# smart_prototyping2.net
KiCad netlist of a schematic drawn in EAGLE
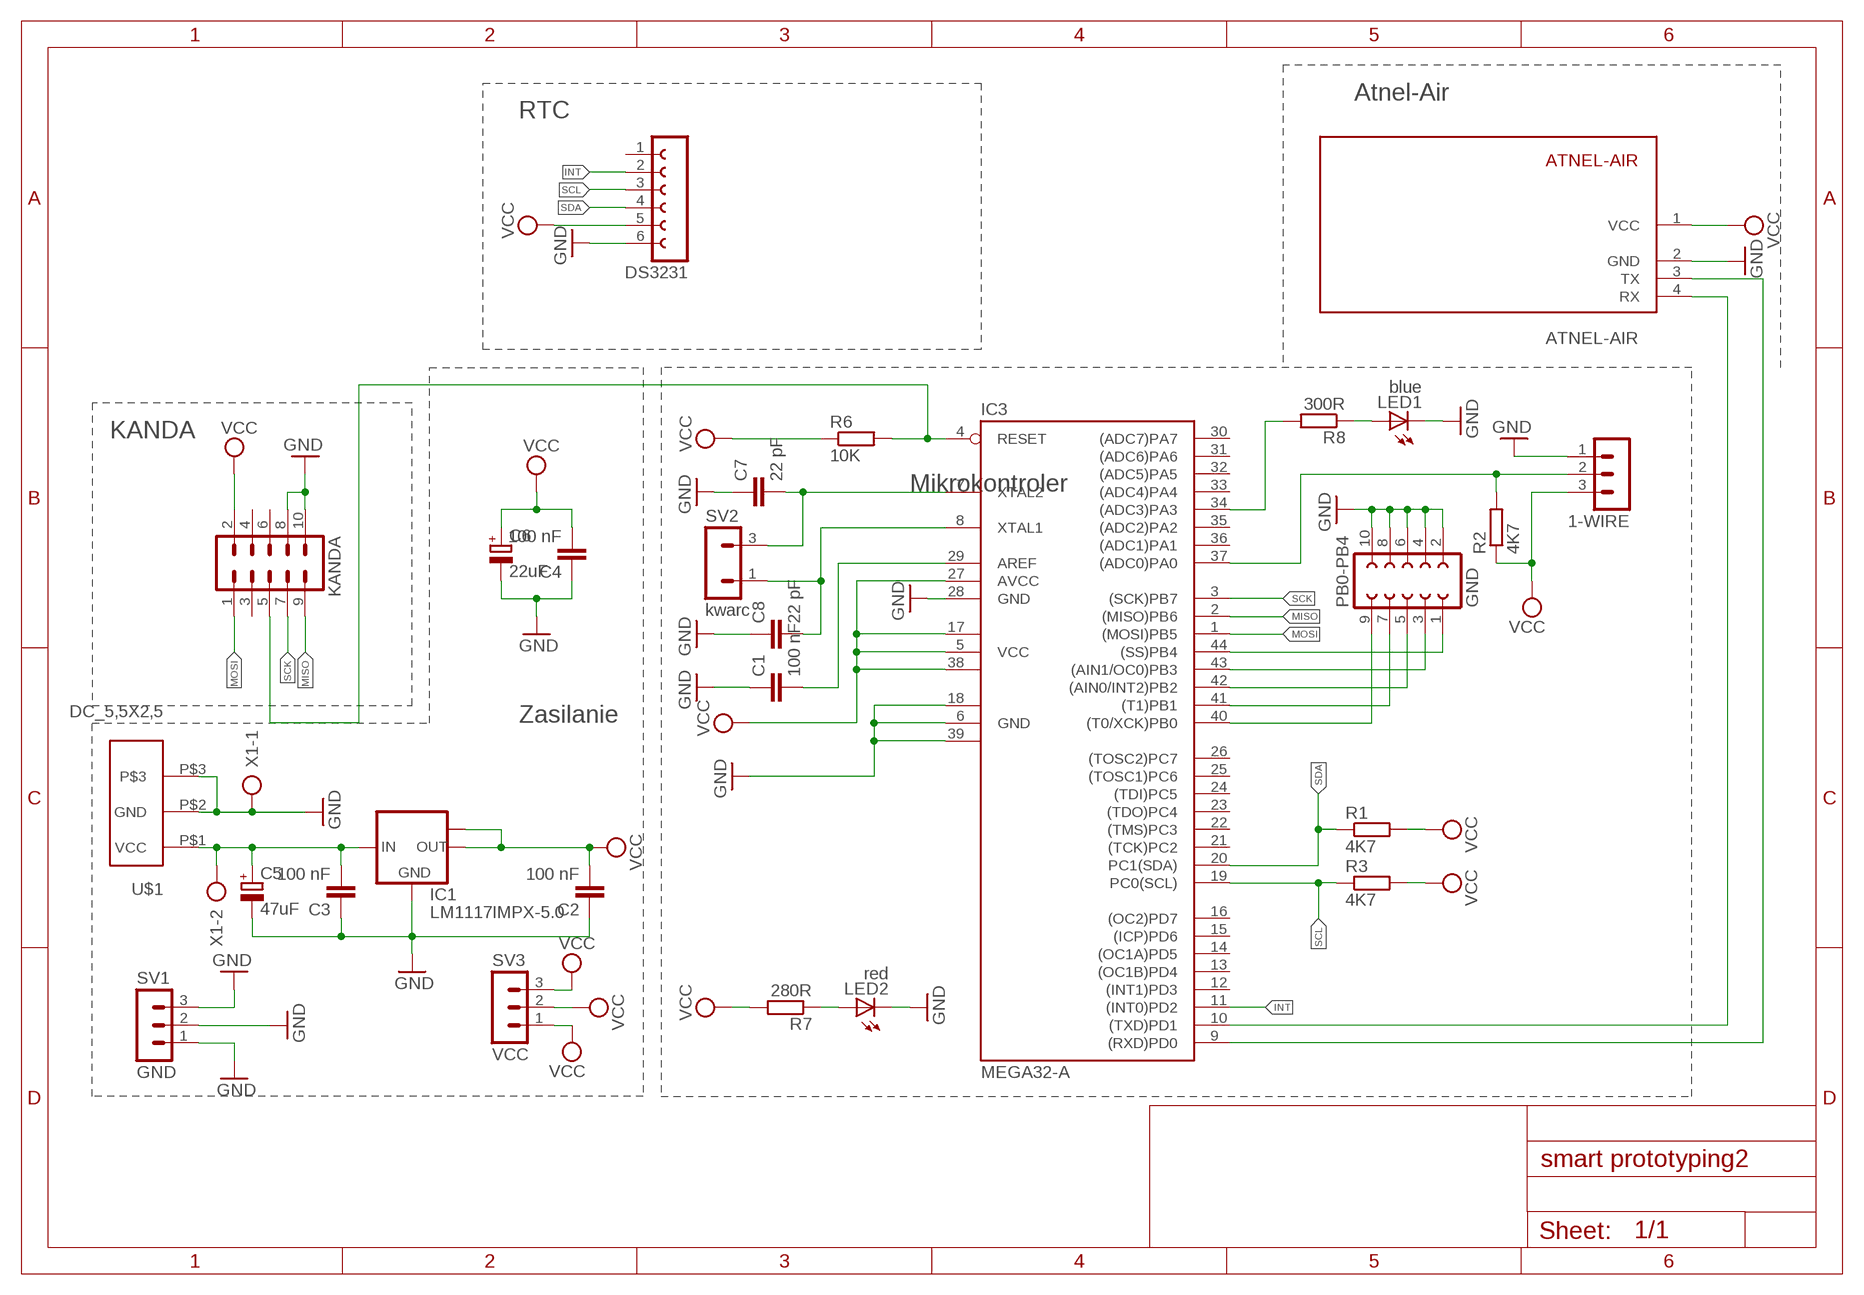
[diagram p0: schematic, sheet 1]

(export (version "E")
  (design (tool "Eeschema 10.0.6"))
  (components
    (comp (ref "1-WIRE")
      (value "MA03-1")
      (footprint "eagle-import:MA03-1")
      (libsource (lib "eagle-import") (part "MA03-1"))
    )
    (comp (ref "ATNEL-AIR")
      (value "ATNEL-AIR")
      (footprint "eagle-import:ATNEL-AIR")
      (libsource (lib "eagle-import") (part "ATNEL-AIR"))
    )
    (comp (ref "C1")
      (value "100 nF")
      (footprint "eagle-import:C0805")
      (libsource (lib "eagle-import") (part "C-EUC0805"))
    )
    (comp (ref "C2")
      (value "100 nF")
      (footprint "eagle-import:C0805")
      (libsource (lib "eagle-import") (part "C-EUC0805"))
    )
    (comp (ref "C3")
      (value "100 nF")
      (footprint "eagle-import:C0805")
      (libsource (lib "eagle-import") (part "C-EUC0805"))
    )
    (comp (ref "C4")
      (value "100 nF")
      (footprint "eagle-import:C0805")
      (libsource (lib "eagle-import") (part "C-EUC0805"))
    )
    (comp (ref "C5")
      (value "47uF")
      (footprint "eagle-import:B45181A")
      (libsource (lib "eagle-import") (part "CPOL-EUB45181A"))
    )
    (comp (ref "C6")
      (value "22uF")
      (footprint "eagle-import:B45181A")
      (libsource (lib "eagle-import") (part "CPOL-EUB45181A"))
    )
    (comp (ref "C7")
      (value "22 pF")
      (footprint "eagle-import:C0805")
      (libsource (lib "eagle-import") (part "C-EUC0805"))
    )
    (comp (ref "C8")
      (value "22 pF")
      (footprint "eagle-import:C0805")
      (libsource (lib "eagle-import") (part "C-EUC0805"))
    )
    (comp (ref "DS3231")
      (value "FE06-1")
      (footprint "eagle-import:FE06")
      (libsource (lib "eagle-import") (part "FE06-1"))
    )
    (comp (ref "IC1")
      (value "LM1117IMPX-5.0")
      (footprint "eagle-import:SOT223")
      (libsource (lib "eagle-import") (part "LM1117IMPX-5.0"))
    )
    (comp (ref "IC3")
      (value "MEGA32-A")
      (footprint "eagle-import:TQFP44")
      (fields (field (name "MPN") "ATMEGA32-16AU"))
      (libsource (lib "eagle-import") (part "MEGA32-A"))
    )
    (comp (ref "KANDA")
      (value "ML10")
      (footprint "eagle-import:ML10")
      (libsource (lib "eagle-import") (part "ML10"))
    )
    (comp (ref "LED1")
      (value "blue")
      (footprint "eagle-import:CHIPLED_1206")
      (libsource (lib "eagle-import") (part "LEDCHIPLED_1206"))
    )
    (comp (ref "LED2")
      (value "red")
      (footprint "eagle-import:CHIPLED_1206")
      (libsource (lib "eagle-import") (part "LEDCHIPLED_1206"))
    )
    (comp (ref "PB0-PB4")
      (value "GND")
      (footprint "eagle-import:FE05-2")
      (libsource (lib "eagle-import") (part "FE05-2"))
    )
    (comp (ref "R1")
      (value "4K7")
      (footprint "eagle-import:R1206W")
      (libsource (lib "eagle-import") (part "R-EU_R1206W"))
    )
    (comp (ref "R2")
      (value "4K7")
      (footprint "eagle-import:R1206W")
      (libsource (lib "eagle-import") (part "R-EU_R1206W"))
    )
    (comp (ref "R3")
      (value "4K7")
      (footprint "eagle-import:R1206W")
      (libsource (lib "eagle-import") (part "R-EU_R1206W"))
    )
    (comp (ref "R6")
      (value "10K")
      (footprint "eagle-import:R1206W")
      (libsource (lib "eagle-import") (part "R-EU_R1206W"))
    )
    (comp (ref "R7")
      (value "280R")
      (footprint "eagle-import:R1206W")
      (libsource (lib "eagle-import") (part "R-EU_R1206W"))
    )
    (comp (ref "R8")
      (value "300R")
      (footprint "eagle-import:R1206W")
      (libsource (lib "eagle-import") (part "R-EU_R1206W"))
    )
    (comp (ref "SV1")
      (value "GND")
      (footprint "eagle-import:MA03-1")
      (libsource (lib "eagle-import") (part "MA03-1"))
    )
    (comp (ref "SV2")
      (value "kwarc")
      (footprint "eagle-import:MA03-1")
      (libsource (lib "eagle-import") (part "con-lstb-wachcio_MA03-1"))
    )
    (comp (ref "SV3")
      (value "VCC")
      (footprint "eagle-import:MA03-1")
      (libsource (lib "eagle-import") (part "MA03-1"))
    )
    (comp (ref "U$1")
      (value "DC_5,5X2,5")
      (footprint "eagle-import:DC_5,5X2,5")
      (libsource (lib "eagle-import") (part "DC_5,5X2,5"))
    )
    (comp (ref "X1")
      (value "AK500/2")
      (footprint "eagle-import:AK500_2")
      (libsource (lib "eagle-import") (part "AK500/2"))
    )
  )
  (nets
    (net (code "1") (name "GND") (class "Default")
      (node (ref "1-WIRE") (pin "1") (pinfunction "1_1") (pintype "passive"))
      (node (ref "ATNEL-AIR") (pin "2") (pinfunction "GND_2") (pintype "bidirectional"))
      (node (ref "C1") (pin "1") (pinfunction "1_1") (pintype "passive"))
      (node (ref "C2") (pin "1") (pinfunction "1_1") (pintype "passive"))
      (node (ref "C3") (pin "1") (pinfunction "1_1") (pintype "passive"))
      (node (ref "C4") (pin "1") (pinfunction "1_1") (pintype "passive"))
      (node (ref "C5") (pin "-") (pinfunction "-_-") (pintype "passive"))
      (node (ref "C6") (pin "-") (pinfunction "-_-") (pintype "passive"))
      (node (ref "C7") (pin "1") (pinfunction "1_1") (pintype "passive"))
      (node (ref "C8") (pin "1") (pinfunction "1_1") (pintype "passive"))
      (node (ref "DS3231") (pin "6") (pinfunction "6_6") (pintype "passive"))
      (node (ref "IC1") (pin "1") (pinfunction "GND_1") (pintype "input"))
      (node (ref "IC3") (pin "18") (pinfunction "GND1_18") (pintype "power_in"))
      (node (ref "IC3") (pin "28") (pinfunction "GND_28") (pintype "power_in"))
      (node (ref "IC3") (pin "39") (pinfunction "GND2_39") (pintype "power_in"))
      (node (ref "IC3") (pin "6") (pinfunction "GND_6") (pintype "power_in"))
      (node (ref "KANDA") (pin "10") (pinfunction "10_10") (pintype "passive"))
      (node (ref "KANDA") (pin "8") (pinfunction "8_8") (pintype "passive"))
      (node (ref "LED1") (pin "C") (pinfunction "C_C") (pintype "passive"))
      (node (ref "LED2") (pin "C") (pinfunction "C_C") (pintype "passive"))
      (node (ref "PB0-PB4") (pin "10") (pinfunction "10_10") (pintype "passive"))
      (node (ref "PB0-PB4") (pin "2") (pinfunction "2_2") (pintype "passive"))
      (node (ref "PB0-PB4") (pin "4") (pinfunction "4_4") (pintype "passive"))
      (node (ref "PB0-PB4") (pin "6") (pinfunction "6_6") (pintype "passive"))
      (node (ref "PB0-PB4") (pin "8") (pinfunction "8_8") (pintype "passive"))
      (node (ref "SV1") (pin "1") (pinfunction "1_1") (pintype "passive"))
      (node (ref "SV1") (pin "2") (pinfunction "2_2") (pintype "passive"))
      (node (ref "SV1") (pin "3") (pinfunction "3_3") (pintype "passive"))
      (node (ref "U$1") (pin "P$2") (pinfunction "GND_P$2") (pintype "bidirectional"))
      (node (ref "U$1") (pin "P$3") (pinfunction "P$3_P$3") (pintype "bidirectional"))
      (node (ref "X1") (pin "1") (pinfunction "KL_1") (pintype "passive"))
    )
    (net (code "2") (name "INT") (class "Default")
      (node (ref "DS3231") (pin "2") (pinfunction "2_2") (pintype "passive"))
      (node (ref "IC3") (pin "11") (pinfunction "(INT0)PD2_11") (pintype "bidirectional"))
    )
    (net (code "3") (name "MISO") (class "Default")
      (node (ref "IC3") (pin "2") (pinfunction "(MISO)PB6_2") (pintype "bidirectional"))
      (node (ref "KANDA") (pin "9") (pinfunction "9_9") (pintype "passive"))
    )
    (net (code "4") (name "MOSI") (class "Default")
      (node (ref "IC3") (pin "1") (pinfunction "(MOSI)PB5_1") (pintype "bidirectional"))
      (node (ref "KANDA") (pin "1") (pinfunction "1_1") (pintype "passive"))
    )
    (net (code "5") (name "Net-(ATNEL-AIR-RX)") (class "Default")
      (node (ref "ATNEL-AIR") (pin "4") (pinfunction "RX_4") (pintype "output"))
      (node (ref "IC3") (pin "10") (pinfunction "(TXD)PD1_10") (pintype "bidirectional"))
    )
    (net (code "6") (name "Net-(ATNEL-AIR-TX)") (class "Default")
      (node (ref "ATNEL-AIR") (pin "3") (pinfunction "TX_3") (pintype "input"))
      (node (ref "IC3") (pin "9") (pinfunction "(RXD)PD0_9") (pintype "bidirectional"))
    )
    (net (code "7") (name "Net-(IC1-IN)") (class "Default")
      (node (ref "C3") (pin "2") (pinfunction "2_2") (pintype "passive"))
      (node (ref "C5") (pin "+") (pinfunction "+_+") (pintype "passive"))
      (node (ref "IC1") (pin "3") (pinfunction "IN_3") (pintype "input"))
      (node (ref "U$1") (pin "P$1") (pinfunction "VCC_P$1") (pintype "bidirectional"))
      (node (ref "X1") (pin "2") (pinfunction "KL_2") (pintype "passive"))
    )
    (net (code "8") (name "Net-(IC3-(ADC0)PA0)") (class "Default")
      (node (ref "1-WIRE") (pin "2") (pinfunction "2_2") (pintype "passive"))
      (node (ref "IC3") (pin "37") (pinfunction "(ADC0)PA0_37") (pintype "bidirectional"))
      (node (ref "R2") (pin "2") (pinfunction "2_2") (pintype "passive"))
    )
    (net (code "9") (name "Net-(IC3-(ADC3)PA3)") (class "Default")
      (node (ref "IC3") (pin "34") (pinfunction "(ADC3)PA3_34") (pintype "bidirectional"))
      (node (ref "R8") (pin "2") (pinfunction "2_2") (pintype "passive"))
    )
    (net (code "10") (name "Net-(IC3-(AIN0{slash}INT2)PB2)") (class "Default")
      (node (ref "IC3") (pin "42") (pinfunction "(AIN0/INT2)PB2_42") (pintype "bidirectional"))
      (node (ref "PB0-PB4") (pin "5") (pinfunction "5_5") (pintype "passive"))
    )
    (net (code "11") (name "Net-(IC3-(AIN1{slash}OC0)PB3)") (class "Default")
      (node (ref "IC3") (pin "43") (pinfunction "(AIN1/OC0)PB3_43") (pintype "bidirectional"))
      (node (ref "PB0-PB4") (pin "3") (pinfunction "3_3") (pintype "passive"))
    )
    (net (code "12") (name "Net-(IC3-(SS)PB4)") (class "Default")
      (node (ref "IC3") (pin "44") (pinfunction "(SS)PB4_44") (pintype "bidirectional"))
      (node (ref "PB0-PB4") (pin "1") (pinfunction "1_1") (pintype "passive"))
    )
    (net (code "13") (name "Net-(IC3-(T0{slash}XCK)PB0)") (class "Default")
      (node (ref "IC3") (pin "40") (pinfunction "(T0/XCK)PB0_40") (pintype "bidirectional"))
      (node (ref "PB0-PB4") (pin "9") (pinfunction "9_9") (pintype "passive"))
    )
    (net (code "14") (name "Net-(IC3-(T1)PB1)") (class "Default")
      (node (ref "IC3") (pin "41") (pinfunction "(T1)PB1_41") (pintype "bidirectional"))
      (node (ref "PB0-PB4") (pin "7") (pinfunction "7_7") (pintype "passive"))
    )
    (net (code "15") (name "Net-(IC3-AREF)") (class "Default")
      (node (ref "C1") (pin "2") (pinfunction "2_2") (pintype "passive"))
      (node (ref "IC3") (pin "29") (pinfunction "AREF_29") (pintype "passive"))
    )
    (net (code "16") (name "Net-(IC3-RESET)") (class "Default")
      (node (ref "IC3") (pin "4") (pinfunction "RESET_4") (pintype "input"))
      (node (ref "KANDA") (pin "5") (pinfunction "5_5") (pintype "passive"))
      (node (ref "R6") (pin "2") (pinfunction "2_2") (pintype "passive"))
    )
    (net (code "17") (name "Net-(IC3-XTAL1)") (class "Default")
      (node (ref "C8") (pin "2") (pinfunction "2_2") (pintype "passive"))
      (node (ref "IC3") (pin "8") (pinfunction "XTAL1_8") (pintype "bidirectional"))
      (node (ref "SV2") (pin "1") (pinfunction "1_1") (pintype "passive"))
    )
    (net (code "18") (name "Net-(IC3-XTAL2)") (class "Default")
      (node (ref "C7") (pin "2") (pinfunction "2_2") (pintype "passive"))
      (node (ref "IC3") (pin "7") (pinfunction "XTAL2_7") (pintype "bidirectional"))
      (node (ref "SV2") (pin "3") (pinfunction "3_3") (pintype "passive"))
    )
    (net (code "19") (name "Net-(LED1-PadA)") (class "Default")
      (node (ref "LED1") (pin "A") (pinfunction "A_A") (pintype "passive"))
      (node (ref "R8") (pin "1") (pinfunction "1_1") (pintype "passive"))
    )
    (net (code "20") (name "Net-(LED2-PadA)") (class "Default")
      (node (ref "LED2") (pin "A") (pinfunction "A_A") (pintype "passive"))
      (node (ref "R7") (pin "1") (pinfunction "1_1") (pintype "passive"))
    )
    (net (code "21") (name "SCK") (class "Default")
      (node (ref "IC3") (pin "3") (pinfunction "(SCK)PB7_3") (pintype "bidirectional"))
      (node (ref "KANDA") (pin "7") (pinfunction "7_7") (pintype "passive"))
    )
    (net (code "22") (name "SCL") (class "Default")
      (node (ref "DS3231") (pin "3") (pinfunction "3_3") (pintype "passive"))
      (node (ref "IC3") (pin "19") (pinfunction "PC0(SCL)_19") (pintype "bidirectional"))
      (node (ref "R3") (pin "1") (pinfunction "1_1") (pintype "passive"))
    )
    (net (code "23") (name "SDA") (class "Default")
      (node (ref "DS3231") (pin "4") (pinfunction "4_4") (pintype "passive"))
      (node (ref "IC3") (pin "20") (pinfunction "PC1(SDA)_20") (pintype "bidirectional"))
      (node (ref "R1") (pin "1") (pinfunction "1_1") (pintype "passive"))
    )
    (net (code "24") (name "VCC") (class "Default")
      (node (ref "1-WIRE") (pin "3") (pinfunction "3_3") (pintype "passive"))
      (node (ref "ATNEL-AIR") (pin "1") (pinfunction "VCC_1") (pintype "bidirectional"))
      (node (ref "C2") (pin "2") (pinfunction "2_2") (pintype "passive"))
      (node (ref "C4") (pin "2") (pinfunction "2_2") (pintype "passive"))
      (node (ref "C6") (pin "+") (pinfunction "+_+") (pintype "passive"))
      (node (ref "DS3231") (pin "5") (pinfunction "5_5") (pintype "passive"))
      (node (ref "IC1") (pin "2") (pinfunction "OUT_2") (pintype "passive"))
      (node (ref "IC1") (pin "TAB") (pinfunction "OUT1_TAB") (pintype "passive"))
      (node (ref "IC3") (pin "17") (pinfunction "VCC1_17") (pintype "power_in"))
      (node (ref "IC3") (pin "27") (pinfunction "AVCC_27") (pintype "power_in"))
      (node (ref "IC3") (pin "38") (pinfunction "VCC2_38") (pintype "power_in"))
      (node (ref "IC3") (pin "5") (pinfunction "VCC_5") (pintype "power_in"))
      (node (ref "KANDA") (pin "2") (pinfunction "2_2") (pintype "passive"))
      (node (ref "R1") (pin "2") (pinfunction "2_2") (pintype "passive"))
      (node (ref "R2") (pin "1") (pinfunction "1_1") (pintype "passive"))
      (node (ref "R3") (pin "2") (pinfunction "2_2") (pintype "passive"))
      (node (ref "R6") (pin "1") (pinfunction "1_1") (pintype "passive"))
      (node (ref "R7") (pin "2") (pinfunction "2_2") (pintype "passive"))
      (node (ref "SV3") (pin "1") (pinfunction "1_1") (pintype "passive"))
      (node (ref "SV3") (pin "2") (pinfunction "2_2") (pintype "passive"))
      (node (ref "SV3") (pin "3") (pinfunction "3_3") (pintype "passive"))
    )
    (net (code "25") (name "unconnected-(DS3231-Pad1)") (class "Default")
      (node (ref "DS3231") (pin "1") (pinfunction "1_1") (pintype "passive"))
    )
    (net (code "26") (name "unconnected-(IC3-(ADC1)PA1-Pad36)") (class "Default")
      (node (ref "IC3") (pin "36") (pinfunction "(ADC1)PA1_36") (pintype "bidirectional"))
    )
    (net (code "27") (name "unconnected-(IC3-(ADC2)PA2-Pad35)") (class "Default")
      (node (ref "IC3") (pin "35") (pinfunction "(ADC2)PA2_35") (pintype "bidirectional"))
    )
    (net (code "28") (name "unconnected-(IC3-(ADC4)PA4-Pad33)") (class "Default")
      (node (ref "IC3") (pin "33") (pinfunction "(ADC4)PA4_33") (pintype "bidirectional"))
    )
    (net (code "29") (name "unconnected-(IC3-(ADC5)PA5-Pad32)") (class "Default")
      (node (ref "IC3") (pin "32") (pinfunction "(ADC5)PA5_32") (pintype "bidirectional"))
    )
    (net (code "30") (name "unconnected-(IC3-(ADC6)PA6-Pad31)") (class "Default")
      (node (ref "IC3") (pin "31") (pinfunction "(ADC6)PA6_31") (pintype "bidirectional"))
    )
    (net (code "31") (name "unconnected-(IC3-(ADC7)PA7-Pad30)") (class "Default")
      (node (ref "IC3") (pin "30") (pinfunction "(ADC7)PA7_30") (pintype "bidirectional"))
    )
    (net (code "32") (name "unconnected-(IC3-(ICP)PD6-Pad15)") (class "Default")
      (node (ref "IC3") (pin "15") (pinfunction "(ICP)PD6_15") (pintype "bidirectional"))
    )
    (net (code "33") (name "unconnected-(IC3-(INT1)PD3-Pad12)") (class "Default")
      (node (ref "IC3") (pin "12") (pinfunction "(INT1)PD3_12") (pintype "bidirectional"))
    )
    (net (code "34") (name "unconnected-(IC3-(OC1A)PD5-Pad14)") (class "Default")
      (node (ref "IC3") (pin "14") (pinfunction "(OC1A)PD5_14") (pintype "bidirectional"))
    )
    (net (code "35") (name "unconnected-(IC3-(OC1B)PD4-Pad13)") (class "Default")
      (node (ref "IC3") (pin "13") (pinfunction "(OC1B)PD4_13") (pintype "bidirectional"))
    )
    (net (code "36") (name "unconnected-(IC3-(OC2)PD7-Pad16)") (class "Default")
      (node (ref "IC3") (pin "16") (pinfunction "(OC2)PD7_16") (pintype "bidirectional"))
    )
    (net (code "37") (name "unconnected-(IC3-(TCK)PC2-Pad21)") (class "Default")
      (node (ref "IC3") (pin "21") (pinfunction "(TCK)PC2_21") (pintype "bidirectional"))
    )
    (net (code "38") (name "unconnected-(IC3-(TDI)PC5-Pad24)") (class "Default")
      (node (ref "IC3") (pin "24") (pinfunction "(TDI)PC5_24") (pintype "bidirectional"))
    )
    (net (code "39") (name "unconnected-(IC3-(TDO)PC4-Pad23)") (class "Default")
      (node (ref "IC3") (pin "23") (pinfunction "(TDO)PC4_23") (pintype "bidirectional"))
    )
    (net (code "40") (name "unconnected-(IC3-(TMS)PC3-Pad22)") (class "Default")
      (node (ref "IC3") (pin "22") (pinfunction "(TMS)PC3_22") (pintype "bidirectional"))
    )
    (net (code "41") (name "unconnected-(IC3-(TOSC1)PC6-Pad25)") (class "Default")
      (node (ref "IC3") (pin "25") (pinfunction "(TOSC1)PC6_25") (pintype "bidirectional"))
    )
    (net (code "42") (name "unconnected-(IC3-(TOSC2)PC7-Pad26)") (class "Default")
      (node (ref "IC3") (pin "26") (pinfunction "(TOSC2)PC7_26") (pintype "bidirectional"))
    )
    (net (code "43") (name "unconnected-(KANDA-Pad3)") (class "Default")
      (node (ref "KANDA") (pin "3") (pinfunction "3_3") (pintype "passive"))
    )
    (net (code "44") (name "unconnected-(KANDA-Pad4)") (class "Default")
      (node (ref "KANDA") (pin "4") (pinfunction "4_4") (pintype "passive"))
    )
    (net (code "45") (name "unconnected-(KANDA-Pad6)") (class "Default")
      (node (ref "KANDA") (pin "6") (pinfunction "6_6") (pintype "passive"))
    )
  )
)
